# SBC_6522_ISA_YM2612_v1.net
KiCad netlist of a schematic drawn in EAGLE
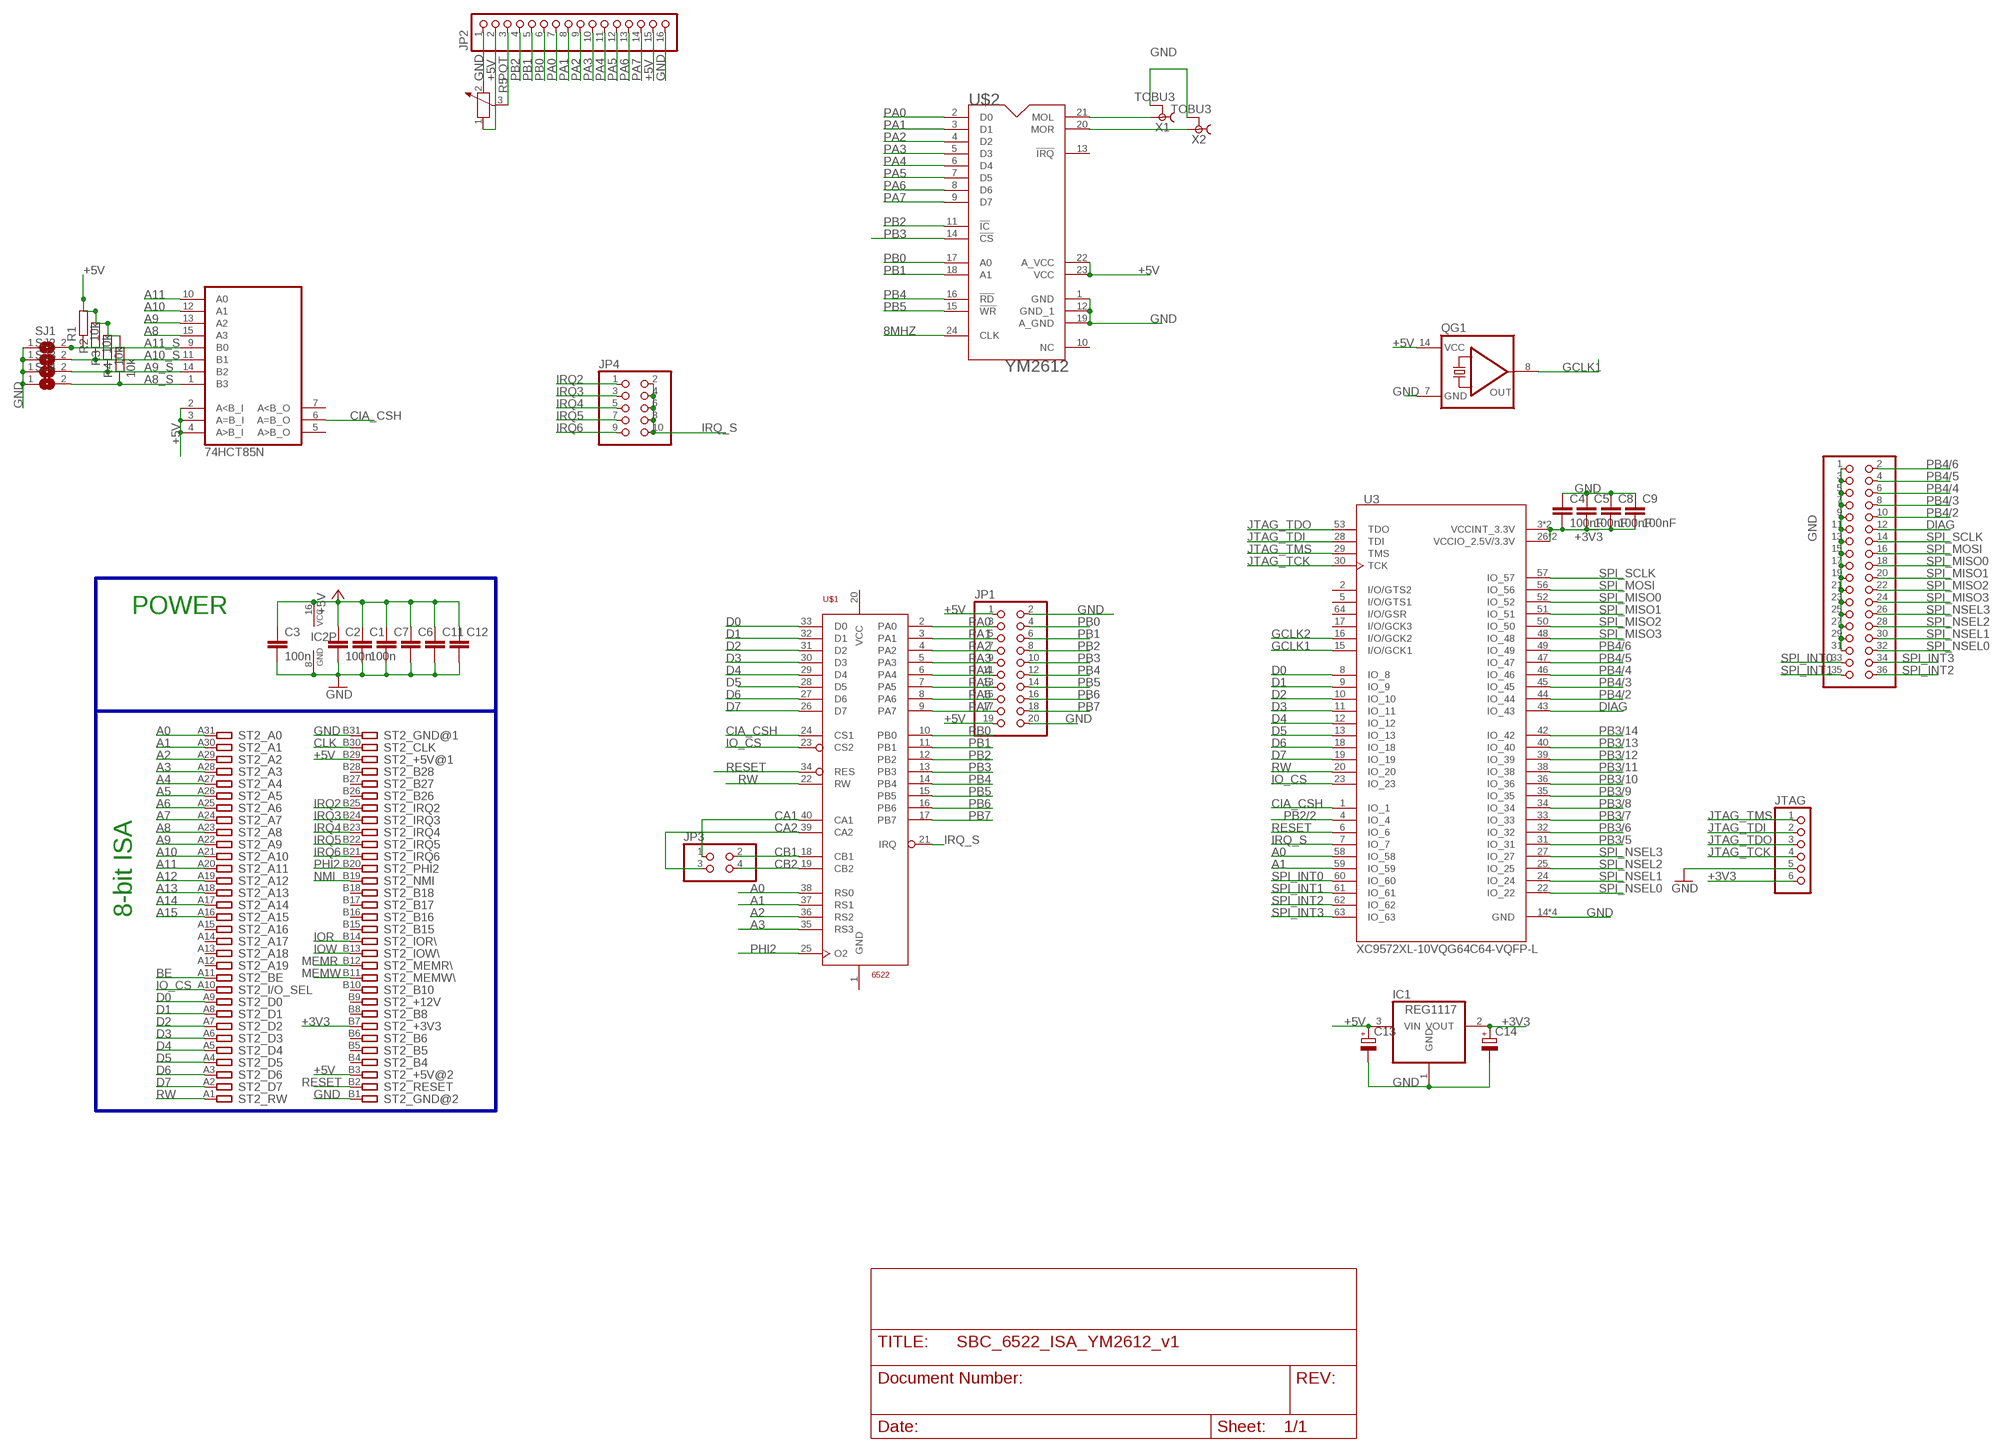
[diagram p0: schematic, sheet 1]

(export (version "E")
  (design (tool "Eeschema 10.0.6"))
  (components
    (comp (ref "C1")
      (value "100n")
      (footprint "eagle-import:C050-025X075")
      (libsource (lib "eagle-import") (part "C-EU050-025X075"))
    )
    (comp (ref "C2")
      (value "100n")
      (footprint "eagle-import:C050-025X075")
      (libsource (lib "eagle-import") (part "C-EU050-025X075"))
    )
    (comp (ref "C3")
      (value "100n")
      (footprint "eagle-import:C050-025X075")
      (libsource (lib "eagle-import") (part "C-EU050-025X075"))
    )
    (comp (ref "C4")
      (value "100nF")
      (footprint "eagle-import:C603")
      (libsource (lib "eagle-import") (part "CAPC603"))
    )
    (comp (ref "C5")
      (value "100nF")
      (footprint "eagle-import:C603")
      (libsource (lib "eagle-import") (part "CAPC603"))
    )
    (comp (ref "C6")
      (value "C-EU050-035X075")
      (footprint "eagle-import:C050-035X075")
      (libsource (lib "eagle-import") (part "rcl_334_C-EU050-035X075"))
    )
    (comp (ref "C7")
      (value "C-EU050-035X075")
      (footprint "eagle-import:C050-035X075")
      (libsource (lib "eagle-import") (part "rcl_334_C-EU050-035X075"))
    )
    (comp (ref "C8")
      (value "100nF")
      (footprint "eagle-import:C603")
      (libsource (lib "eagle-import") (part "CAPC603"))
    )
    (comp (ref "C9")
      (value "100nF")
      (footprint "eagle-import:C603")
      (libsource (lib "eagle-import") (part "CAPC603"))
    )
    (comp (ref "C11")
      (value "C-EU050-035X075")
      (footprint "eagle-import:C050-035X075")
      (libsource (lib "eagle-import") (part "rcl_334_C-EU050-035X075"))
    )
    (comp (ref "C12")
      (value "C-EU050-035X075")
      (footprint "eagle-import:C050-035X075")
      (libsource (lib "eagle-import") (part "rcl_334_C-EU050-035X075"))
    )
    (comp (ref "C13")
      (value "CPOL-EUE2.5-5")
      (footprint "eagle-import:E2,5-5")
      (libsource (lib "eagle-import") (part "CPOL-EUE2.5-5"))
    )
    (comp (ref "C14")
      (value "CPOL-EUE2.5-5")
      (footprint "eagle-import:E2,5-5")
      (libsource (lib "eagle-import") (part "CPOL-EUE2.5-5"))
    )
    (comp (ref "IC1")
      (value "REG1117")
      (footprint "eagle-import:SOT223")
      (libsource (lib "eagle-import") (part "REG1117"))
    )
    (comp (ref "IC2")
      (value "74HCT85N")
      (footprint "eagle-import:DIL16")
      (libsource (lib "eagle-import") (part "7485NHCT"))
    )
    (comp (ref "JP1")
      (value "PINHD-2X10")
      (footprint "eagle-import:2X10")
      (libsource (lib "eagle-import") (part "PINHD-2X10"))
    )
    (comp (ref "JP2")
      (value "PINHD-1X16")
      (footprint "eagle-import:1X16")
      (libsource (lib "eagle-import") (part "PINHD-1X16"))
    )
    (comp (ref "JP3")
      (value "PINHD-2X2")
      (footprint "eagle-import:2X02")
      (libsource (lib "eagle-import") (part "PINHD-2X2"))
    )
    (comp (ref "JP4")
      (value "PINHD-2X5")
      (footprint "eagle-import:2X05")
      (libsource (lib "eagle-import") (part "PINHD-2X5"))
    )
    (comp (ref "JP5")
      (value "PINHD-2X18")
      (footprint "eagle-import:2X18")
      (libsource (lib "eagle-import") (part "PINHD-2X18"))
    )
    (comp (ref "JTAG")
      (value "PINHD-1X6")
      (footprint "eagle-import:1X06")
      (libsource (lib "eagle-import") (part "PINHD-1X6"))
    )
    (comp (ref "QG1")
      (value "QG5860")
      (footprint "eagle-import:DIL14S")
      (libsource (lib "eagle-import") (part "QG5860"))
    )
    (comp (ref "R1")
      (value "10k")
      (footprint "eagle-import:0207_7")
      (libsource (lib "eagle-import") (part "R-EU_0207/7"))
    )
    (comp (ref "R2")
      (value "10k")
      (footprint "eagle-import:0207_7")
      (libsource (lib "eagle-import") (part "R-EU_0207/7"))
    )
    (comp (ref "R3")
      (value "10k")
      (footprint "eagle-import:0207_7")
      (libsource (lib "eagle-import") (part "R-EU_0207/7"))
    )
    (comp (ref "R4")
      (value "10k")
      (footprint "eagle-import:0207_7")
      (libsource (lib "eagle-import") (part "R-EU_0207/7"))
    )
    (comp (ref "R5")
      (value "POTENTIOMETER_PT-10")
      (footprint "eagle-import:PT-10")
      (libsource (lib "eagle-import") (part "POTENTIOMETER_PT-10"))
    )
    (comp (ref "SJ1") (value "SJ") (footprint "eagle-import:SJ") (libsource (lib "eagle-import") (part "SJ")))
    (comp (ref "SJ2") (value "SJ") (footprint "eagle-import:SJ") (libsource (lib "eagle-import") (part "SJ")))
    (comp (ref "SJ3") (value "SJ") (footprint "eagle-import:SJ") (libsource (lib "eagle-import") (part "SJ")))
    (comp (ref "SJ4") (value "SJ") (footprint "eagle-import:SJ") (libsource (lib "eagle-import") (part "SJ")))
    (comp (ref "ST2")
      (value "IBM8BIT_ISASHORT")
      (footprint "eagle-import:APP_2X32_SHORT")
      (libsource (lib "eagle-import") (part "IBM8BIT_ISASHORT"))
    )
    (comp (ref "U$1")
      (value "6522")
      (footprint "eagle-import:6522")
      (libsource (lib "eagle-import") (part "6522"))
    )
    (comp (ref "U$2")
      (value "YM2612")
      (footprint "eagle-import:DIL24")
      (libsource (lib "eagle-import") (part "YM2612"))
    )
    (comp (ref "U3")
      (value "XC9572XL-10VQG64C64-VQFP-L")
      (footprint "eagle-import:VQFP64")
      (fields
        (field (name "DIGIKEY_PARTNO") "122-1388-ND")
        (field (name "MANUFACTURER") "Xilinx Inc")
        (field (name "MPN") "XC9572XL-10VQG64C")
        (field (name "CREATED_BY") "PCBLayout.com")
      )
      (libsource (lib "eagle-import") (part "XC9572XL-10VQG64C64-VQFP-L"))
    )
    (comp (ref "X1")
      (value "TOBU3")
      (footprint "eagle-import:TOBU3")
      (fields (field (name "MF") "FARNELL") (field (name "MPN") "TOBU 3"))
      (libsource (lib "eagle-import") (part "TOBU3"))
    )
    (comp (ref "X2")
      (value "TOBU3")
      (footprint "eagle-import:TOBU3")
      (fields (field (name "MF") "FARNELL") (field (name "MPN") "TOBU 3"))
      (libsource (lib "eagle-import") (part "TOBU3"))
    )
  )
  (nets
    (net (code "1") (name "+5V") (class "Default")
      (node (ref "C1") (pin "1") (pinfunction "1_1") (pintype "passive"))
      (node (ref "C11") (pin "1") (pinfunction "1_1") (pintype "passive"))
      (node (ref "C12") (pin "1") (pinfunction "1_1") (pintype "passive"))
      (node (ref "C13") (pin "+") (pinfunction "+_+") (pintype "passive"))
      (node (ref "C2") (pin "1") (pinfunction "1_1") (pintype "passive"))
      (node (ref "C3") (pin "1") (pinfunction "1_1") (pintype "passive"))
      (node (ref "C6") (pin "1") (pinfunction "1_1") (pintype "passive"))
      (node (ref "C7") (pin "1") (pinfunction "1_1") (pintype "passive"))
      (node (ref "IC1") (pin "3") (pinfunction "VIN_3") (pintype "input"))
      (node (ref "IC2") (pin "16") (pinfunction "VCC_16") (pintype "power_in"))
      (node (ref "IC2") (pin "2") (pinfunction "A<B_I_2") (pintype "input"))
      (node (ref "IC2") (pin "3") (pinfunction "A=B_I_3") (pintype "input"))
      (node (ref "IC2") (pin "4") (pinfunction "A>B_I_4") (pintype "input"))
      (node (ref "JP1") (pin "1") (pinfunction "1_1") (pintype "passive"))
      (node (ref "JP1") (pin "19") (pinfunction "19_19") (pintype "passive"))
      (node (ref "JP2") (pin "15") (pinfunction "15_15") (pintype "passive"))
      (node (ref "JP2") (pin "2") (pinfunction "2_2") (pintype "passive"))
      (node (ref "QG1") (pin "14") (pinfunction "VCC_14") (pintype "power_in"))
      (node (ref "R1") (pin "2") (pinfunction "2_2") (pintype "passive"))
      (node (ref "R2") (pin "2") (pinfunction "2_2") (pintype "passive"))
      (node (ref "R3") (pin "2") (pinfunction "2_2") (pintype "passive"))
      (node (ref "R4") (pin "2") (pinfunction "2_2") (pintype "passive"))
      (node (ref "R5") (pin "1") (pinfunction "1_1") (pintype "passive"))
      (node (ref "ST2") (pin "B29") (pinfunction "P_B29") (pintype "bidirectional"))
      (node (ref "ST2") (pin "B3") (pinfunction "P_B3") (pintype "bidirectional"))
      (node (ref "U$2") (pin "22") (pinfunction "A_VCC_22") (pintype "bidirectional"))
      (node (ref "U$2") (pin "23") (pinfunction "VCC_23") (pintype "bidirectional"))
    )
    (net (code "2") (name "/+3V3") (class "Default")
      (node (ref "C14") (pin "+") (pinfunction "+_+") (pintype "passive"))
      (node (ref "C4") (pin "2") (pinfunction "2_2") (pintype "passive"))
      (node (ref "C5") (pin "2") (pinfunction "2_2") (pintype "passive"))
      (node (ref "C8") (pin "2") (pinfunction "2_2") (pintype "passive"))
      (node (ref "C9") (pin "2") (pinfunction "2_2") (pintype "passive"))
      (node (ref "IC1") (pin "2") (pinfunction "VOUT_2") (pintype "output"))
      (node (ref "JTAG") (pin "6") (pinfunction "6_6") (pintype "passive"))
      (node (ref "ST2") (pin "B7") (pinfunction "P_B7") (pintype "bidirectional"))
      (node (ref "U3") (pin "26") (pinfunction "VCCIO_2.5V/3.3V_26") (pintype "power_in"))
      (node (ref "U3") (pin "3") (pinfunction "VCCINT_3.3V_3") (pintype "power_in"))
      (node (ref "U3") (pin "37") (pinfunction "VCCINT_3.3V_37") (pintype "power_in"))
      (node (ref "U3") (pin "55") (pinfunction "VCCIO_2.5V/3.3V_55") (pintype "power_in"))
    )
    (net (code "3") (name "/8MHZ") (class "Default")
      (node (ref "U$2") (pin "24") (pinfunction "CLK_24") (pintype "bidirectional"))
    )
    (net (code "4") (name "/A0") (class "Default")
      (node (ref "ST2") (pin "A31") (pinfunction "P_A31") (pintype "bidirectional"))
      (node (ref "U$1") (pin "38") (pinfunction "RS0_38") (pintype "input"))
      (node (ref "U3") (pin "58") (pinfunction "IO_58_58") (pintype "bidirectional"))
    )
    (net (code "5") (name "/A1") (class "Default")
      (node (ref "ST2") (pin "A30") (pinfunction "P_A30") (pintype "bidirectional"))
      (node (ref "U$1") (pin "37") (pinfunction "RS1_37") (pintype "input"))
      (node (ref "U3") (pin "59") (pinfunction "IO_59_59") (pintype "bidirectional"))
    )
    (net (code "6") (name "/A2") (class "Default")
      (node (ref "ST2") (pin "A29") (pinfunction "P_A29") (pintype "bidirectional"))
      (node (ref "U$1") (pin "36") (pinfunction "RS2_36") (pintype "input"))
    )
    (net (code "7") (name "/A3") (class "Default")
      (node (ref "ST2") (pin "A28") (pinfunction "P_A28") (pintype "bidirectional"))
      (node (ref "U$1") (pin "35") (pinfunction "RS3_35") (pintype "input"))
    )
    (net (code "8") (name "/A4") (class "Default")
      (node (ref "ST2") (pin "A27") (pinfunction "P_A27") (pintype "bidirectional"))
    )
    (net (code "9") (name "/A5") (class "Default")
      (node (ref "ST2") (pin "A26") (pinfunction "P_A26") (pintype "bidirectional"))
    )
    (net (code "10") (name "/A6") (class "Default")
      (node (ref "ST2") (pin "A25") (pinfunction "P_A25") (pintype "bidirectional"))
    )
    (net (code "11") (name "/A7") (class "Default")
      (node (ref "ST2") (pin "A24") (pinfunction "P_A24") (pintype "bidirectional"))
    )
    (net (code "12") (name "/A8") (class "Default")
      (node (ref "IC2") (pin "15") (pinfunction "A3_15") (pintype "input"))
      (node (ref "ST2") (pin "A23") (pinfunction "P_A23") (pintype "bidirectional"))
    )
    (net (code "13") (name "/A8_S") (class "Default")
      (node (ref "IC2") (pin "1") (pinfunction "B3_1") (pintype "input"))
      (node (ref "R4") (pin "1") (pinfunction "1_1") (pintype "passive"))
      (node (ref "SJ4") (pin "2") (pinfunction "2_2") (pintype "passive"))
    )
    (net (code "14") (name "/A9") (class "Default")
      (node (ref "IC2") (pin "13") (pinfunction "A2_13") (pintype "input"))
      (node (ref "ST2") (pin "A22") (pinfunction "P_A22") (pintype "bidirectional"))
    )
    (net (code "15") (name "/A9_S") (class "Default")
      (node (ref "IC2") (pin "14") (pinfunction "B2_14") (pintype "input"))
      (node (ref "R3") (pin "1") (pinfunction "1_1") (pintype "passive"))
      (node (ref "SJ3") (pin "2") (pinfunction "2_2") (pintype "passive"))
    )
    (net (code "16") (name "/A10") (class "Default")
      (node (ref "IC2") (pin "12") (pinfunction "A1_12") (pintype "input"))
      (node (ref "ST2") (pin "A21") (pinfunction "P_A21") (pintype "bidirectional"))
    )
    (net (code "17") (name "/A10_S") (class "Default")
      (node (ref "IC2") (pin "11") (pinfunction "B1_11") (pintype "input"))
      (node (ref "R2") (pin "1") (pinfunction "1_1") (pintype "passive"))
      (node (ref "SJ2") (pin "2") (pinfunction "2_2") (pintype "passive"))
    )
    (net (code "18") (name "/A11") (class "Default")
      (node (ref "IC2") (pin "10") (pinfunction "A0_10") (pintype "input"))
      (node (ref "ST2") (pin "A20") (pinfunction "P_A20") (pintype "bidirectional"))
    )
    (net (code "19") (name "/A11_S") (class "Default")
      (node (ref "IC2") (pin "9") (pinfunction "B0_9") (pintype "input"))
      (node (ref "R1") (pin "1") (pinfunction "1_1") (pintype "passive"))
      (node (ref "SJ1") (pin "2") (pinfunction "2_2") (pintype "passive"))
    )
    (net (code "20") (name "/A12") (class "Default")
      (node (ref "ST2") (pin "A19") (pinfunction "P_A19") (pintype "bidirectional"))
    )
    (net (code "21") (name "/A13") (class "Default")
      (node (ref "ST2") (pin "A18") (pinfunction "P_A18") (pintype "bidirectional"))
    )
    (net (code "22") (name "/A14") (class "Default")
      (node (ref "ST2") (pin "A17") (pinfunction "P_A17") (pintype "bidirectional"))
    )
    (net (code "23") (name "/A15") (class "Default")
      (node (ref "ST2") (pin "A16") (pinfunction "P_A16") (pintype "bidirectional"))
    )
    (net (code "24") (name "/BE") (class "Default")
      (node (ref "ST2") (pin "A11") (pinfunction "P_A11") (pintype "bidirectional"))
    )
    (net (code "25") (name "/CA1") (class "Default")
      (node (ref "JP3") (pin "1") (pinfunction "1_1") (pintype "passive"))
      (node (ref "U$1") (pin "40") (pinfunction "CA1_40") (pintype "input"))
    )
    (net (code "26") (name "/CA2") (class "Default")
      (node (ref "JP3") (pin "3") (pinfunction "3_3") (pintype "passive"))
      (node (ref "U$1") (pin "39") (pinfunction "CA2_39") (pintype "input"))
    )
    (net (code "27") (name "/CB1") (class "Default")
      (node (ref "JP3") (pin "2") (pinfunction "2_2") (pintype "passive"))
      (node (ref "U$1") (pin "18") (pinfunction "CB1_18") (pintype "input"))
    )
    (net (code "28") (name "/CB2") (class "Default")
      (node (ref "JP3") (pin "4") (pinfunction "4_4") (pintype "passive"))
      (node (ref "U$1") (pin "19") (pinfunction "CB2_19") (pintype "input"))
    )
    (net (code "29") (name "/CIA_CSH") (class "Default")
      (node (ref "IC2") (pin "6") (pinfunction "A=B_O_6") (pintype "output"))
      (node (ref "U$1") (pin "24") (pinfunction "CS1_24") (pintype "input"))
      (node (ref "U3") (pin "1") (pinfunction "IO_1_1") (pintype "bidirectional"))
    )
    (net (code "30") (name "/CLK") (class "Default")
      (node (ref "ST2") (pin "B30") (pinfunction "P_B30") (pintype "bidirectional"))
    )
    (net (code "31") (name "/D0") (class "Default")
      (node (ref "ST2") (pin "A9") (pinfunction "P_A9") (pintype "bidirectional"))
      (node (ref "U$1") (pin "33") (pinfunction "D0_33") (pintype "bidirectional"))
      (node (ref "U3") (pin "8") (pinfunction "IO_8_8") (pintype "bidirectional"))
    )
    (net (code "32") (name "/D1") (class "Default")
      (node (ref "ST2") (pin "A8") (pinfunction "P_A8") (pintype "bidirectional"))
      (node (ref "U$1") (pin "32") (pinfunction "D1_32") (pintype "bidirectional"))
      (node (ref "U3") (pin "9") (pinfunction "IO_9_9") (pintype "bidirectional"))
    )
    (net (code "33") (name "/D2") (class "Default")
      (node (ref "ST2") (pin "A7") (pinfunction "P_A7") (pintype "bidirectional"))
      (node (ref "U$1") (pin "31") (pinfunction "D2_31") (pintype "bidirectional"))
      (node (ref "U3") (pin "10") (pinfunction "IO_10_10") (pintype "bidirectional"))
    )
    (net (code "34") (name "/D3") (class "Default")
      (node (ref "ST2") (pin "A6") (pinfunction "P_A6") (pintype "bidirectional"))
      (node (ref "U$1") (pin "30") (pinfunction "D3_30") (pintype "bidirectional"))
      (node (ref "U3") (pin "11") (pinfunction "IO_11_11") (pintype "bidirectional"))
    )
    (net (code "35") (name "/D4") (class "Default")
      (node (ref "ST2") (pin "A5") (pinfunction "P_A5") (pintype "bidirectional"))
      (node (ref "U$1") (pin "29") (pinfunction "D4_29") (pintype "bidirectional"))
      (node (ref "U3") (pin "12") (pinfunction "IO_12_12") (pintype "bidirectional"))
    )
    (net (code "36") (name "/D5") (class "Default")
      (node (ref "ST2") (pin "A4") (pinfunction "P_A4") (pintype "bidirectional"))
      (node (ref "U$1") (pin "28") (pinfunction "D5_28") (pintype "bidirectional"))
      (node (ref "U3") (pin "13") (pinfunction "IO_13_13") (pintype "bidirectional"))
    )
    (net (code "37") (name "/D6") (class "Default")
      (node (ref "ST2") (pin "A3") (pinfunction "P_A3") (pintype "bidirectional"))
      (node (ref "U$1") (pin "27") (pinfunction "D6_27") (pintype "bidirectional"))
      (node (ref "U3") (pin "18") (pinfunction "IO_18_18") (pintype "bidirectional"))
    )
    (net (code "38") (name "/D7") (class "Default")
      (node (ref "ST2") (pin "A2") (pinfunction "P_A2") (pintype "bidirectional"))
      (node (ref "U$1") (pin "26") (pinfunction "D7_26") (pintype "bidirectional"))
      (node (ref "U3") (pin "19") (pinfunction "IO_19_19") (pintype "bidirectional"))
    )
    (net (code "39") (name "/DIAG") (class "Default")
      (node (ref "JP5") (pin "12") (pinfunction "12_12") (pintype "passive"))
      (node (ref "U3") (pin "43") (pinfunction "IO_43_43") (pintype "bidirectional"))
    )
    (net (code "40") (name "/GCLK1") (class "Default")
      (node (ref "QG1") (pin "8") (pinfunction "OUT_8") (pintype "output"))
      (node (ref "U3") (pin "15") (pinfunction "I/O/GCK1_15") (pintype "bidirectional"))
    )
    (net (code "41") (name "/GCLK2") (class "Default")
      (node (ref "U3") (pin "16") (pinfunction "I/O/GCK2_16") (pintype "bidirectional"))
    )
    (net (code "42") (name "/IOR") (class "Default")
      (node (ref "ST2") (pin "B14") (pinfunction "P_B14") (pintype "bidirectional"))
    )
    (net (code "43") (name "/IOW") (class "Default")
      (node (ref "ST2") (pin "B13") (pinfunction "P_B13") (pintype "bidirectional"))
    )
    (net (code "44") (name "/IO_CS") (class "Default")
      (node (ref "ST2") (pin "A10") (pinfunction "P_A10") (pintype "bidirectional"))
      (node (ref "U$1") (pin "23") (pinfunction "CS2_23") (pintype "input"))
      (node (ref "U3") (pin "23") (pinfunction "IO_23_23") (pintype "bidirectional"))
    )
    (net (code "45") (name "/IRQ2") (class "Default")
      (node (ref "JP4") (pin "1") (pinfunction "1_1") (pintype "passive"))
      (node (ref "ST2") (pin "B25") (pinfunction "P_B25") (pintype "bidirectional"))
    )
    (net (code "46") (name "/IRQ3") (class "Default")
      (node (ref "JP4") (pin "3") (pinfunction "3_3") (pintype "passive"))
      (node (ref "ST2") (pin "B24") (pinfunction "P_B24") (pintype "bidirectional"))
    )
    (net (code "47") (name "/IRQ4") (class "Default")
      (node (ref "JP4") (pin "5") (pinfunction "5_5") (pintype "passive"))
      (node (ref "ST2") (pin "B23") (pinfunction "P_B23") (pintype "bidirectional"))
    )
    (net (code "48") (name "/IRQ5") (class "Default")
      (node (ref "JP4") (pin "7") (pinfunction "7_7") (pintype "passive"))
      (node (ref "ST2") (pin "B22") (pinfunction "P_B22") (pintype "bidirectional"))
    )
    (net (code "49") (name "/IRQ6") (class "Default")
      (node (ref "JP4") (pin "9") (pinfunction "9_9") (pintype "passive"))
      (node (ref "ST2") (pin "B21") (pinfunction "P_B21") (pintype "bidirectional"))
    )
    (net (code "50") (name "/IRQ_S") (class "Default")
      (node (ref "JP4") (pin "10") (pinfunction "10_10") (pintype "passive"))
      (node (ref "JP4") (pin "2") (pinfunction "2_2") (pintype "passive"))
      (node (ref "JP4") (pin "4") (pinfunction "4_4") (pintype "passive"))
      (node (ref "JP4") (pin "6") (pinfunction "6_6") (pintype "passive"))
      (node (ref "JP4") (pin "8") (pinfunction "8_8") (pintype "passive"))
      (node (ref "U$1") (pin "21") (pinfunction "IRQ_21") (pintype "output"))
      (node (ref "U3") (pin "7") (pinfunction "IO_7_7") (pintype "bidirectional"))
    )
    (net (code "51") (name "/JTAG_TCK") (class "Default")
      (node (ref "JTAG") (pin "4") (pinfunction "4_4") (pintype "passive"))
      (node (ref "U3") (pin "30") (pinfunction "TCK_30") (pintype "input"))
    )
    (net (code "52") (name "/JTAG_TDI") (class "Default")
      (node (ref "JTAG") (pin "2") (pinfunction "2_2") (pintype "passive"))
      (node (ref "U3") (pin "28") (pinfunction "TDI_28") (pintype "input"))
    )
    (net (code "53") (name "/JTAG_TDO") (class "Default")
      (node (ref "JTAG") (pin "3") (pinfunction "3_3") (pintype "passive"))
      (node (ref "U3") (pin "53") (pinfunction "TDO_53") (pintype "input"))
    )
    (net (code "54") (name "/JTAG_TMS") (class "Default")
      (node (ref "JTAG") (pin "1") (pinfunction "1_1") (pintype "passive"))
      (node (ref "U3") (pin "29") (pinfunction "TMS_29") (pintype "input"))
    )
    (net (code "55") (name "/MEMR") (class "Default")
      (node (ref "ST2") (pin "B12") (pinfunction "P_B12") (pintype "bidirectional"))
    )
    (net (code "56") (name "/MEMW") (class "Default")
      (node (ref "ST2") (pin "B11") (pinfunction "P_B11") (pintype "bidirectional"))
    )
    (net (code "57") (name "/NMI") (class "Default")
      (node (ref "ST2") (pin "B19") (pinfunction "P_B19") (pintype "bidirectional"))
    )
    (net (code "58") (name "/PA0") (class "Default")
      (node (ref "JP1") (pin "3") (pinfunction "3_3") (pintype "passive"))
      (node (ref "JP2") (pin "7") (pinfunction "7_7") (pintype "passive"))
      (node (ref "U$1") (pin "2") (pinfunction "PA0_2") (pintype "bidirectional"))
      (node (ref "U$2") (pin "2") (pinfunction "D0_2") (pintype "bidirectional"))
    )
    (net (code "59") (name "/PA1") (class "Default")
      (node (ref "JP1") (pin "5") (pinfunction "5_5") (pintype "passive"))
      (node (ref "JP2") (pin "8") (pinfunction "8_8") (pintype "passive"))
      (node (ref "U$1") (pin "3") (pinfunction "PA1_3") (pintype "bidirectional"))
      (node (ref "U$2") (pin "3") (pinfunction "D1_3") (pintype "bidirectional"))
    )
    (net (code "60") (name "/PA2") (class "Default")
      (node (ref "JP1") (pin "7") (pinfunction "7_7") (pintype "passive"))
      (node (ref "JP2") (pin "9") (pinfunction "9_9") (pintype "passive"))
      (node (ref "U$1") (pin "4") (pinfunction "PA2_4") (pintype "bidirectional"))
      (node (ref "U$2") (pin "4") (pinfunction "D2_4") (pintype "bidirectional"))
    )
    (net (code "61") (name "/PA3") (class "Default")
      (node (ref "JP1") (pin "9") (pinfunction "9_9") (pintype "passive"))
      (node (ref "JP2") (pin "10") (pinfunction "10_10") (pintype "passive"))
      (node (ref "U$1") (pin "5") (pinfunction "PA3_5") (pintype "bidirectional"))
      (node (ref "U$2") (pin "5") (pinfunction "D3_5") (pintype "bidirectional"))
    )
    (net (code "62") (name "/PA4") (class "Default")
      (node (ref "JP1") (pin "11") (pinfunction "11_11") (pintype "passive"))
      (node (ref "JP2") (pin "11") (pinfunction "11_11") (pintype "passive"))
      (node (ref "U$1") (pin "6") (pinfunction "PA4_6") (pintype "bidirectional"))
      (node (ref "U$2") (pin "6") (pinfunction "D4_6") (pintype "bidirectional"))
    )
    (net (code "63") (name "/PA5") (class "Default")
      (node (ref "JP1") (pin "13") (pinfunction "13_13") (pintype "passive"))
      (node (ref "JP2") (pin "12") (pinfunction "12_12") (pintype "passive"))
      (node (ref "U$1") (pin "7") (pinfunction "PA5_7") (pintype "bidirectional"))
      (node (ref "U$2") (pin "7") (pinfunction "D5_7") (pintype "bidirectional"))
    )
    (net (code "64") (name "/PA6") (class "Default")
      (node (ref "JP1") (pin "15") (pinfunction "15_15") (pintype "passive"))
      (node (ref "JP2") (pin "13") (pinfunction "13_13") (pintype "passive"))
      (node (ref "U$1") (pin "8") (pinfunction "PA6_8") (pintype "bidirectional"))
      (node (ref "U$2") (pin "8") (pinfunction "D6_8") (pintype "bidirectional"))
    )
    (net (code "65") (name "/PA7") (class "Default")
      (node (ref "JP1") (pin "17") (pinfunction "17_17") (pintype "passive"))
      (node (ref "JP2") (pin "14") (pinfunction "14_14") (pintype "passive"))
      (node (ref "U$1") (pin "9") (pinfunction "PA7_9") (pintype "bidirectional"))
      (node (ref "U$2") (pin "9") (pinfunction "D7_9") (pintype "bidirectional"))
    )
    (net (code "66") (name "/PB0") (class "Default")
      (node (ref "JP1") (pin "4") (pinfunction "4_4") (pintype "passive"))
      (node (ref "JP2") (pin "6") (pinfunction "6_6") (pintype "passive"))
      (node (ref "U$1") (pin "10") (pinfunction "PB0_10") (pintype "bidirectional"))
      (node (ref "U$2") (pin "17") (pinfunction "A0_17") (pintype "bidirectional"))
    )
    (net (code "67") (name "/PB1") (class "Default")
      (node (ref "JP1") (pin "6") (pinfunction "6_6") (pintype "passive"))
      (node (ref "JP2") (pin "5") (pinfunction "5_5") (pintype "passive"))
      (node (ref "U$1") (pin "11") (pinfunction "PB1_11") (pintype "bidirectional"))
      (node (ref "U$2") (pin "18") (pinfunction "A1_18") (pintype "bidirectional"))
    )
    (net (code "68") (name "/PB2") (class "Default")
      (node (ref "JP1") (pin "8") (pinfunction "8_8") (pintype "passive"))
      (node (ref "JP2") (pin "4") (pinfunction "4_4") (pintype "passive"))
      (node (ref "U$1") (pin "12") (pinfunction "PB2_12") (pintype "bidirectional"))
      (node (ref "U$2") (pin "11") (pinfunction "~{IC}_11") (pintype "bidirectional"))
    )
    (net (code "69") (name "/PB2{slash}2") (class "Default")
      (node (ref "U3") (pin "4") (pinfunction "IO_4_4") (pintype "bidirectional"))
    )
    (net (code "70") (name "/PB3") (class "Default")
      (node (ref "JP1") (pin "10") (pinfunction "10_10") (pintype "passive"))
      (node (ref "U$1") (pin "13") (pinfunction "PB3_13") (pintype "bidirectional"))
      (node (ref "U$2") (pin "14") (pinfunction "~{CS}_14") (pintype "bidirectional"))
    )
    (net (code "71") (name "/PB3{slash}5") (class "Default")
      (node (ref "U3") (pin "31") (pinfunction "IO_31_31") (pintype "bidirectional"))
    )
    (net (code "72") (name "/PB3{slash}6") (class "Default")
      (node (ref "U3") (pin "32") (pinfunction "IO_32_32") (pintype "bidirectional"))
    )
    (net (code "73") (name "/PB3{slash}7") (class "Default")
      (node (ref "U3") (pin "33") (pinfunction "IO_33_33") (pintype "bidirectional"))
    )
    (net (code "74") (name "/PB3{slash}8") (class "Default")
      (node (ref "U3") (pin "34") (pinfunction "IO_34_34") (pintype "bidirectional"))
    )
    (net (code "75") (name "/PB3{slash}9") (class "Default")
      (node (ref "U3") (pin "35") (pinfunction "IO_35_35") (pintype "bidirectional"))
    )
    (net (code "76") (name "/PB3{slash}10") (class "Default")
      (node (ref "U3") (pin "36") (pinfunction "IO_36_36") (pintype "bidirectional"))
    )
    (net (code "77") (name "/PB3{slash}11") (class "Default")
      (node (ref "U3") (pin "38") (pinfunction "IO_38_38") (pintype "bidirectional"))
    )
    (net (code "78") (name "/PB3{slash}12") (class "Default")
      (node (ref "U3") (pin "39") (pinfunction "IO_39_39") (pintype "bidirectional"))
    )
    (net (code "79") (name "/PB3{slash}13") (class "Default")
      (node (ref "U3") (pin "40") (pinfunction "IO_40_40") (pintype "bidirectional"))
    )
    (net (code "80") (name "/PB3{slash}14") (class "Default")
      (node (ref "U3") (pin "42") (pinfunction "IO_42_42") (pintype "bidirectional"))
    )
    (net (code "81") (name "/PB4") (class "Default")
      (node (ref "JP1") (pin "12") (pinfunction "12_12") (pintype "passive"))
      (node (ref "U$1") (pin "14") (pinfunction "PB4_14") (pintype "bidirectional"))
      (node (ref "U$2") (pin "16") (pinfunction "~{RD}_16") (pintype "bidirectional"))
    )
    (net (code "82") (name "/PB4{slash}2") (class "Default")
      (node (ref "JP5") (pin "10") (pinfunction "10_10") (pintype "passive"))
      (node (ref "U3") (pin "44") (pinfunction "IO_44_44") (pintype "bidirectional"))
    )
    (net (code "83") (name "/PB4{slash}3") (class "Default")
      (node (ref "JP5") (pin "8") (pinfunction "8_8") (pintype "passive"))
      (node (ref "U3") (pin "45") (pinfunction "IO_45_45") (pintype "bidirectional"))
    )
    (net (code "84") (name "/PB4{slash}4") (class "Default")
      (node (ref "JP5") (pin "6") (pinfunction "6_6") (pintype "passive"))
      (node (ref "U3") (pin "46") (pinfunction "IO_46_46") (pintype "bidirectional"))
    )
    (net (code "85") (name "/PB4{slash}5") (class "Default")
      (node (ref "JP5") (pin "4") (pinfunction "4_4") (pintype "passive"))
      (node (ref "U3") (pin "47") (pinfunction "IO_47_47") (pintype "bidirectional"))
    )
    (net (code "86") (name "/PB4{slash}6") (class "Default")
      (node (ref "JP5") (pin "2") (pinfunction "2_2") (pintype "passive"))
      (node (ref "U3") (pin "49") (pinfunction "IO_49_49") (pintype "bidirectional"))
    )
    (net (code "87") (name "/PB5") (class "Default")
      (node (ref "JP1") (pin "14") (pinfunction "14_14") (pintype "passive"))
      (node (ref "U$1") (pin "15") (pinfunction "PB5_15") (pintype "bidirectional"))
      (node (ref "U$2") (pin "15") (pinfunction "~{WR}_15") (pintype "bidirectional"))
    )
    (net (code "88") (name "/PB6") (class "Default")
      (node (ref "JP1") (pin "16") (pinfunction "16_16") (pintype "passive"))
      (node (ref "U$1") (pin "16") (pinfunction "PB6_16") (pintype "bidirectional"))
    )
    (net (code "89") (name "/PB7") (class "Default")
      (node (ref "JP1") (pin "18") (pinfunction "18_18") (pintype "passive"))
      (node (ref "U$1") (pin "17") (pinfunction "PB7_17") (pintype "bidirectional"))
    )
    (net (code "90") (name "/PHI2") (class "Default")
      (node (ref "ST2") (pin "B20") (pinfunction "P_B20") (pintype "bidirectional"))
      (node (ref "U$1") (pin "25") (pinfunction "O2_25") (pintype "bidirectional"))
    )
    (net (code "91") (name "/POT") (class "Default")
      (node (ref "JP2") (pin "3") (pinfunction "3_3") (pintype "passive"))
      (node (ref "R5") (pin "3") (pinfunction "3_3") (pintype "passive"))
    )
    (net (code "92") (name "/RESET") (class "Default")
      (node (ref "ST2") (pin "B2") (pinfunction "P_B2") (pintype "bidirectional"))
      (node (ref "U$1") (pin "34") (pinfunction "RES_34") (pintype "input"))
      (node (ref "U3") (pin "6") (pinfunction "IO_6_6") (pintype "bidirectional"))
    )
    (net (code "93") (name "/RW") (class "Default")
      (node (ref "ST2") (pin "A1") (pinfunction "P_A1") (pintype "bidirectional"))
      (node (ref "U$1") (pin "22") (pinfunction "RW_22") (pintype "input"))
      (node (ref "U3") (pin "20") (pinfunction "IO_20_20") (pintype "bidirectional"))
    )
    (net (code "94") (name "/SPI_INT0") (class "Default")
      (node (ref "JP5") (pin "33") (pinfunction "33_33") (pintype "passive"))
      (node (ref "U3") (pin "60") (pinfunction "IO_60_60") (pintype "bidirectional"))
    )
    (net (code "95") (name "/SPI_INT1") (class "Default")
      (node (ref "JP5") (pin "35") (pinfunction "35_35") (pintype "passive"))
      (node (ref "U3") (pin "61") (pinfunction "IO_61_61") (pintype "bidirectional"))
    )
    (net (code "96") (name "/SPI_INT2") (class "Default")
      (node (ref "JP5") (pin "36") (pinfunction "36_36") (pintype "passive"))
      (node (ref "U3") (pin "62") (pinfunction "IO_62_62") (pintype "bidirectional"))
    )
    (net (code "97") (name "/SPI_INT3") (class "Default")
      (node (ref "JP5") (pin "34") (pinfunction "34_34") (pintype "passive"))
      (node (ref "U3") (pin "63") (pinfunction "IO_63_63") (pintype "bidirectional"))
    )
    (net (code "98") (name "/SPI_MISO0") (class "Default")
      (node (ref "JP5") (pin "18") (pinfunction "18_18") (pintype "passive"))
      (node (ref "U3") (pin "52") (pinfunction "IO_52_52") (pintype "bidirectional"))
    )
    (net (code "99") (name "/SPI_MISO1") (class "Default")
      (node (ref "JP5") (pin "20") (pinfunction "20_20") (pintype "passive"))
      (node (ref "U3") (pin "51") (pinfunction "IO_51_51") (pintype "bidirectional"))
    )
    (net (code "100") (name "/SPI_MISO2") (class "Default")
      (node (ref "JP5") (pin "22") (pinfunction "22_22") (pintype "passive"))
      (node (ref "U3") (pin "50") (pinfunction "IO_50_50") (pintype "bidirectional"))
    )
    (net (code "101") (name "/SPI_MISO3") (class "Default")
      (node (ref "JP5") (pin "24") (pinfunction "24_24") (pintype "passive"))
      (node (ref "U3") (pin "48") (pinfunction "IO_48_48") (pintype "bidirectional"))
    )
    (net (code "102") (name "/SPI_MOSI") (class "Default")
      (node (ref "JP5") (pin "16") (pinfunction "16_16") (pintype "passive"))
      (node (ref "U3") (pin "56") (pinfunction "IO_56_56") (pintype "bidirectional"))
    )
    (net (code "103") (name "/SPI_NSEL0") (class "Default")
      (node (ref "JP5") (pin "32") (pinfunction "32_32") (pintype "passive"))
      (node (ref "U3") (pin "22") (pinfunction "IO_22_22") (pintype "bidirectional"))
    )
    (net (code "104") (name "/SPI_NSEL1") (class "Default")
      (node (ref "JP5") (pin "30") (pinfunction "30_30") (pintype "passive"))
      (node (ref "U3") (pin "24") (pinfunction "IO_24_24") (pintype "bidirectional"))
    )
    (net (code "105") (name "/SPI_NSEL2") (class "Default")
      (node (ref "JP5") (pin "28") (pinfunction "28_28") (pintype "passive"))
      (node (ref "U3") (pin "25") (pinfunction "IO_25_25") (pintype "bidirectional"))
    )
    (net (code "106") (name "/SPI_NSEL3") (class "Default")
      (node (ref "JP5") (pin "26") (pinfunction "26_26") (pintype "passive"))
      (node (ref "U3") (pin "27") (pinfunction "IO_27_27") (pintype "bidirectional"))
    )
    (net (code "107") (name "/SPI_SCLK") (class "Default")
      (node (ref "JP5") (pin "14") (pinfunction "14_14") (pintype "passive"))
      (node (ref "U3") (pin "57") (pinfunction "IO_57_57") (pintype "bidirectional"))
    )
    (net (code "108") (name "GND") (class "Default")
      (node (ref "C1") (pin "2") (pinfunction "2_2") (pintype "passive"))
      (node (ref "C11") (pin "2") (pinfunction "2_2") (pintype "passive"))
      (node (ref "C12") (pin "2") (pinfunction "2_2") (pintype "passive"))
      (node (ref "C13") (pin "-") (pinfunction "-_-") (pintype "passive"))
      (node (ref "C14") (pin "-") (pinfunction "-_-") (pintype "passive"))
      (node (ref "C2") (pin "2") (pinfunction "2_2") (pintype "passive"))
      (node (ref "C3") (pin "2") (pinfunction "2_2") (pintype "passive"))
      (node (ref "C4") (pin "1") (pinfunction "1_1") (pintype "passive"))
      (node (ref "C5") (pin "1") (pinfunction "1_1") (pintype "passive"))
      (node (ref "C6") (pin "2") (pinfunction "2_2") (pintype "passive"))
      (node (ref "C7") (pin "2") (pinfunction "2_2") (pintype "passive"))
      (node (ref "C8") (pin "1") (pinfunction "1_1") (pintype "passive"))
      (node (ref "C9") (pin "1") (pinfunction "1_1") (pintype "passive"))
      (node (ref "IC1") (pin "1") (pinfunction "GND_1") (pintype "power_in"))
      (node (ref "IC2") (pin "8") (pinfunction "GND_8") (pintype "power_in"))
      (node (ref "JP1") (pin "2") (pinfunction "2_2") (pintype "passive"))
      (node (ref "JP1") (pin "20") (pinfunction "20_20") (pintype "passive"))
      (node (ref "JP2") (pin "1") (pinfunction "1_1") (pintype "passive"))
      (node (ref "JP2") (pin "16") (pinfunction "16_16") (pintype "passive"))
      (node (ref "JP5") (pin "1") (pinfunction "1_1") (pintype "passive"))
      (node (ref "JP5") (pin "11") (pinfunction "11_11") (pintype "passive"))
      (node (ref "JP5") (pin "13") (pinfunction "13_13") (pintype "passive"))
      (node (ref "JP5") (pin "15") (pinfunction "15_15") (pintype "passive"))
      (node (ref "JP5") (pin "17") (pinfunction "17_17") (pintype "passive"))
      (node (ref "JP5") (pin "19") (pinfunction "19_19") (pintype "passive"))
      (node (ref "JP5") (pin "21") (pinfunction "21_21") (pintype "passive"))
      (node (ref "JP5") (pin "23") (pinfunction "23_23") (pintype "passive"))
      (node (ref "JP5") (pin "25") (pinfunction "25_25") (pintype "passive"))
      (node (ref "JP5") (pin "27") (pinfunction "27_27") (pintype "passive"))
      (node (ref "JP5") (pin "29") (pinfunction "29_29") (pintype "passive"))
      (node (ref "JP5") (pin "3") (pinfunction "3_3") (pintype "passive"))
      (node (ref "JP5") (pin "31") (pinfunction "31_31") (pintype "passive"))
      (node (ref "JP5") (pin "5") (pinfunction "5_5") (pintype "passive"))
      (node (ref "JP5") (pin "7") (pinfunction "7_7") (pintype "passive"))
      (node (ref "JP5") (pin "9") (pinfunction "9_9") (pintype "passive"))
      (node (ref "JTAG") (pin "5") (pinfunction "5_5") (pintype "passive"))
      (node (ref "QG1") (pin "7") (pinfunction "GND_7") (pintype "power_in"))
      (node (ref "R5") (pin "2") (pinfunction "2_2") (pintype "passive"))
      (node (ref "SJ1") (pin "1") (pinfunction "1_1") (pintype "passive"))
      (node (ref "SJ2") (pin "1") (pinfunction "1_1") (pintype "passive"))
      (node (ref "SJ3") (pin "1") (pinfunction "1_1") (pintype "passive"))
      (node (ref "SJ4") (pin "1") (pinfunction "1_1") (pintype "passive"))
      (node (ref "ST2") (pin "B1") (pinfunction "P_B1") (pintype "bidirectional"))
      (node (ref "ST2") (pin "B31") (pinfunction "P_B31") (pintype "bidirectional"))
      (node (ref "U$2") (pin "1") (pinfunction "GND_1") (pintype "bidirectional"))
      (node (ref "U$2") (pin "12") (pinfunction "GND_1_12") (pintype "bidirectional"))
      (node (ref "U$2") (pin "19") (pinfunction "A_GND_19") (pintype "bidirectional"))
      (node (ref "U3") (pin "14") (pinfunction "GND_14") (pintype "power_in"))
      (node (ref "U3") (pin "21") (pinfunction "GND_21") (pintype "power_in"))
      (node (ref "U3") (pin "41") (pinfunction "GND_41") (pintype "power_in"))
      (node (ref "U3") (pin "54") (pinfunction "GND_54") (pintype "power_in"))
      (node (ref "X1") (pin "2") (pinfunction "2_2") (pintype "passive"))
      (node (ref "X1") (pin "2@1") (pinfunction "2_2@1") (pintype "passive"))
      (node (ref "X1") (pin "2@2") (pinfunction "2_2@2") (pintype "passive"))
      (node (ref "X2") (pin "2") (pinfunction "2_2") (pintype "passive"))
      (node (ref "X2") (pin "2@1") (pinfunction "2_2@1") (pintype "passive"))
      (node (ref "X2") (pin "2@2") (pinfunction "2_2@2") (pintype "passive"))
    )
    (net (code "109") (name "Net-(U$2-MOL)") (class "Default")
      (node (ref "U$2") (pin "21") (pinfunction "MOL_21") (pintype "bidirectional"))
      (node (ref "X1") (pin "1") (pinfunction "1_1") (pintype "passive"))
    )
    (net (code "110") (name "Net-(U$2-MOR)") (class "Default")
      (node (ref "U$2") (pin "20") (pinfunction "MOR_20") (pintype "bidirectional"))
      (node (ref "X2") (pin "1") (pinfunction "1_1") (pintype "passive"))
    )
    (net (code "111") (name "unconnected-(IC2A-A<B_O-Pad7)") (class "Default")
      (node (ref "IC2") (pin "7") (pinfunction "A<B_O_7") (pintype "output"))
    )
    (net (code "112") (name "unconnected-(IC2A-A>B_O-Pad5)") (class "Default")
      (node (ref "IC2") (pin "5") (pinfunction "A>B_O_5") (pintype "output"))
    )
    (net (code "113") (name "unconnected-(ST2A-P-PadB9)") (class "Default")
      (node (ref "ST2") (pin "B9") (pinfunction "P_B9") (pintype "bidirectional"))
    )
    (net (code "114") (name "unconnected-(ST2AA-P-PadB16)") (class "Default")
      (node (ref "ST2") (pin "B16") (pinfunction "P_B16") (pintype "bidirectional"))
    )
    (net (code "115") (name "unconnected-(ST2AB-P-PadB17)") (class "Default")
      (node (ref "ST2") (pin "B17") (pinfunction "P_B17") (pintype "bidirectional"))
    )
    (net (code "116") (name "unconnected-(ST2AC-P-PadB18)") (class "Default")
      (node (ref "ST2") (pin "B18") (pinfunction "P_B18") (pintype "bidirectional"))
    )
    (net (code "117") (name "unconnected-(ST2AD-P-PadB26)") (class "Default")
      (node (ref "ST2") (pin "B26") (pinfunction "P_B26") (pintype "bidirectional"))
    )
    (net (code "118") (name "unconnected-(ST2AE-P-PadB27)") (class "Default")
      (node (ref "ST2") (pin "B27") (pinfunction "P_B27") (pintype "bidirectional"))
    )
    (net (code "119") (name "unconnected-(ST2AF-P-PadB28)") (class "Default")
      (node (ref "ST2") (pin "B28") (pinfunction "P_B28") (pintype "bidirectional"))
    )
    (net (code "120") (name "unconnected-(ST2AG-P-PadB4)") (class "Default")
      (node (ref "ST2") (pin "B4") (pinfunction "P_B4") (pintype "bidirectional"))
    )
    (net (code "121") (name "unconnected-(ST2AH-P-PadB5)") (class "Default")
      (node (ref "ST2") (pin "B5") (pinfunction "P_B5") (pintype "bidirectional"))
    )
    (net (code "122") (name "unconnected-(ST2AI-P-PadB6)") (class "Default")
      (node (ref "ST2") (pin "B6") (pinfunction "P_B6") (pintype "bidirectional"))
    )
    (net (code "123") (name "unconnected-(ST2AJ-P-PadB8)") (class "Default")
      (node (ref "ST2") (pin "B8") (pinfunction "P_B8") (pintype "bidirectional"))
    )
    (net (code "124") (name "unconnected-(ST2M-P-PadA15)") (class "Default")
      (node (ref "ST2") (pin "A15") (pinfunction "P_A15") (pintype "bidirectional"))
    )
    (net (code "125") (name "unconnected-(ST2N-P-PadA14)") (class "Default")
      (node (ref "ST2") (pin "A14") (pinfunction "P_A14") (pintype "bidirectional"))
    )
    (net (code "126") (name "unconnected-(ST2O-P-PadA13)") (class "Default")
      (node (ref "ST2") (pin "A13") (pinfunction "P_A13") (pintype "bidirectional"))
    )
    (net (code "127") (name "unconnected-(ST2P-P-PadA12)") (class "Default")
      (node (ref "ST2") (pin "A12") (pinfunction "P_A12") (pintype "bidirectional"))
    )
    (net (code "128") (name "unconnected-(ST2Y-P-PadB10)") (class "Default")
      (node (ref "ST2") (pin "B10") (pinfunction "P_B10") (pintype "bidirectional"))
    )
    (net (code "129") (name "unconnected-(ST2Z-P-PadB15)") (class "Default")
      (node (ref "ST2") (pin "B15") (pinfunction "P_B15") (pintype "bidirectional"))
    )
    (net (code "130") (name "unconnected-(U$1-GND-Pad1)") (class "Default")
      (node (ref "U$1") (pin "1") (pinfunction "GND_1") (pintype "bidirectional"))
    )
    (net (code "131") (name "unconnected-(U$1-VCC-Pad20)") (class "Default")
      (node (ref "U$1") (pin "20") (pinfunction "VCC_20") (pintype "bidirectional"))
    )
    (net (code "132") (name "unconnected-(U$2-NC-Pad10)") (class "Default")
      (node (ref "U$2") (pin "10") (pinfunction "NC_10") (pintype "bidirectional"))
    )
    (net (code "133") (name "unconnected-(U$2-~{IRQ}-Pad13)") (class "Default")
      (node (ref "U$2") (pin "13") (pinfunction "~{IRQ}_13") (pintype "bidirectional"))
    )
    (net (code "134") (name "unconnected-(U3-I{slash}O{slash}GCK3-Pad17)") (class "Default")
      (node (ref "U3") (pin "17") (pinfunction "I/O/GCK3_17") (pintype "bidirectional"))
    )
    (net (code "135") (name "unconnected-(U3-I{slash}O{slash}GSR-Pad64)") (class "Default")
      (node (ref "U3") (pin "64") (pinfunction "I/O/GSR_64") (pintype "bidirectional"))
    )
    (net (code "136") (name "unconnected-(U3-I{slash}O{slash}GTS1-Pad5)") (class "Default")
      (node (ref "U3") (pin "5") (pinfunction "I/O/GTS1_5") (pintype "bidirectional"))
    )
    (net (code "137") (name "unconnected-(U3-I{slash}O{slash}GTS2-Pad2)") (class "Default")
      (node (ref "U3") (pin "2") (pinfunction "I/O/GTS2_2") (pintype "bidirectional"))
    )
  )
)
